# Design1.net
KiCad netlist of a schematic drawn in EAGLE
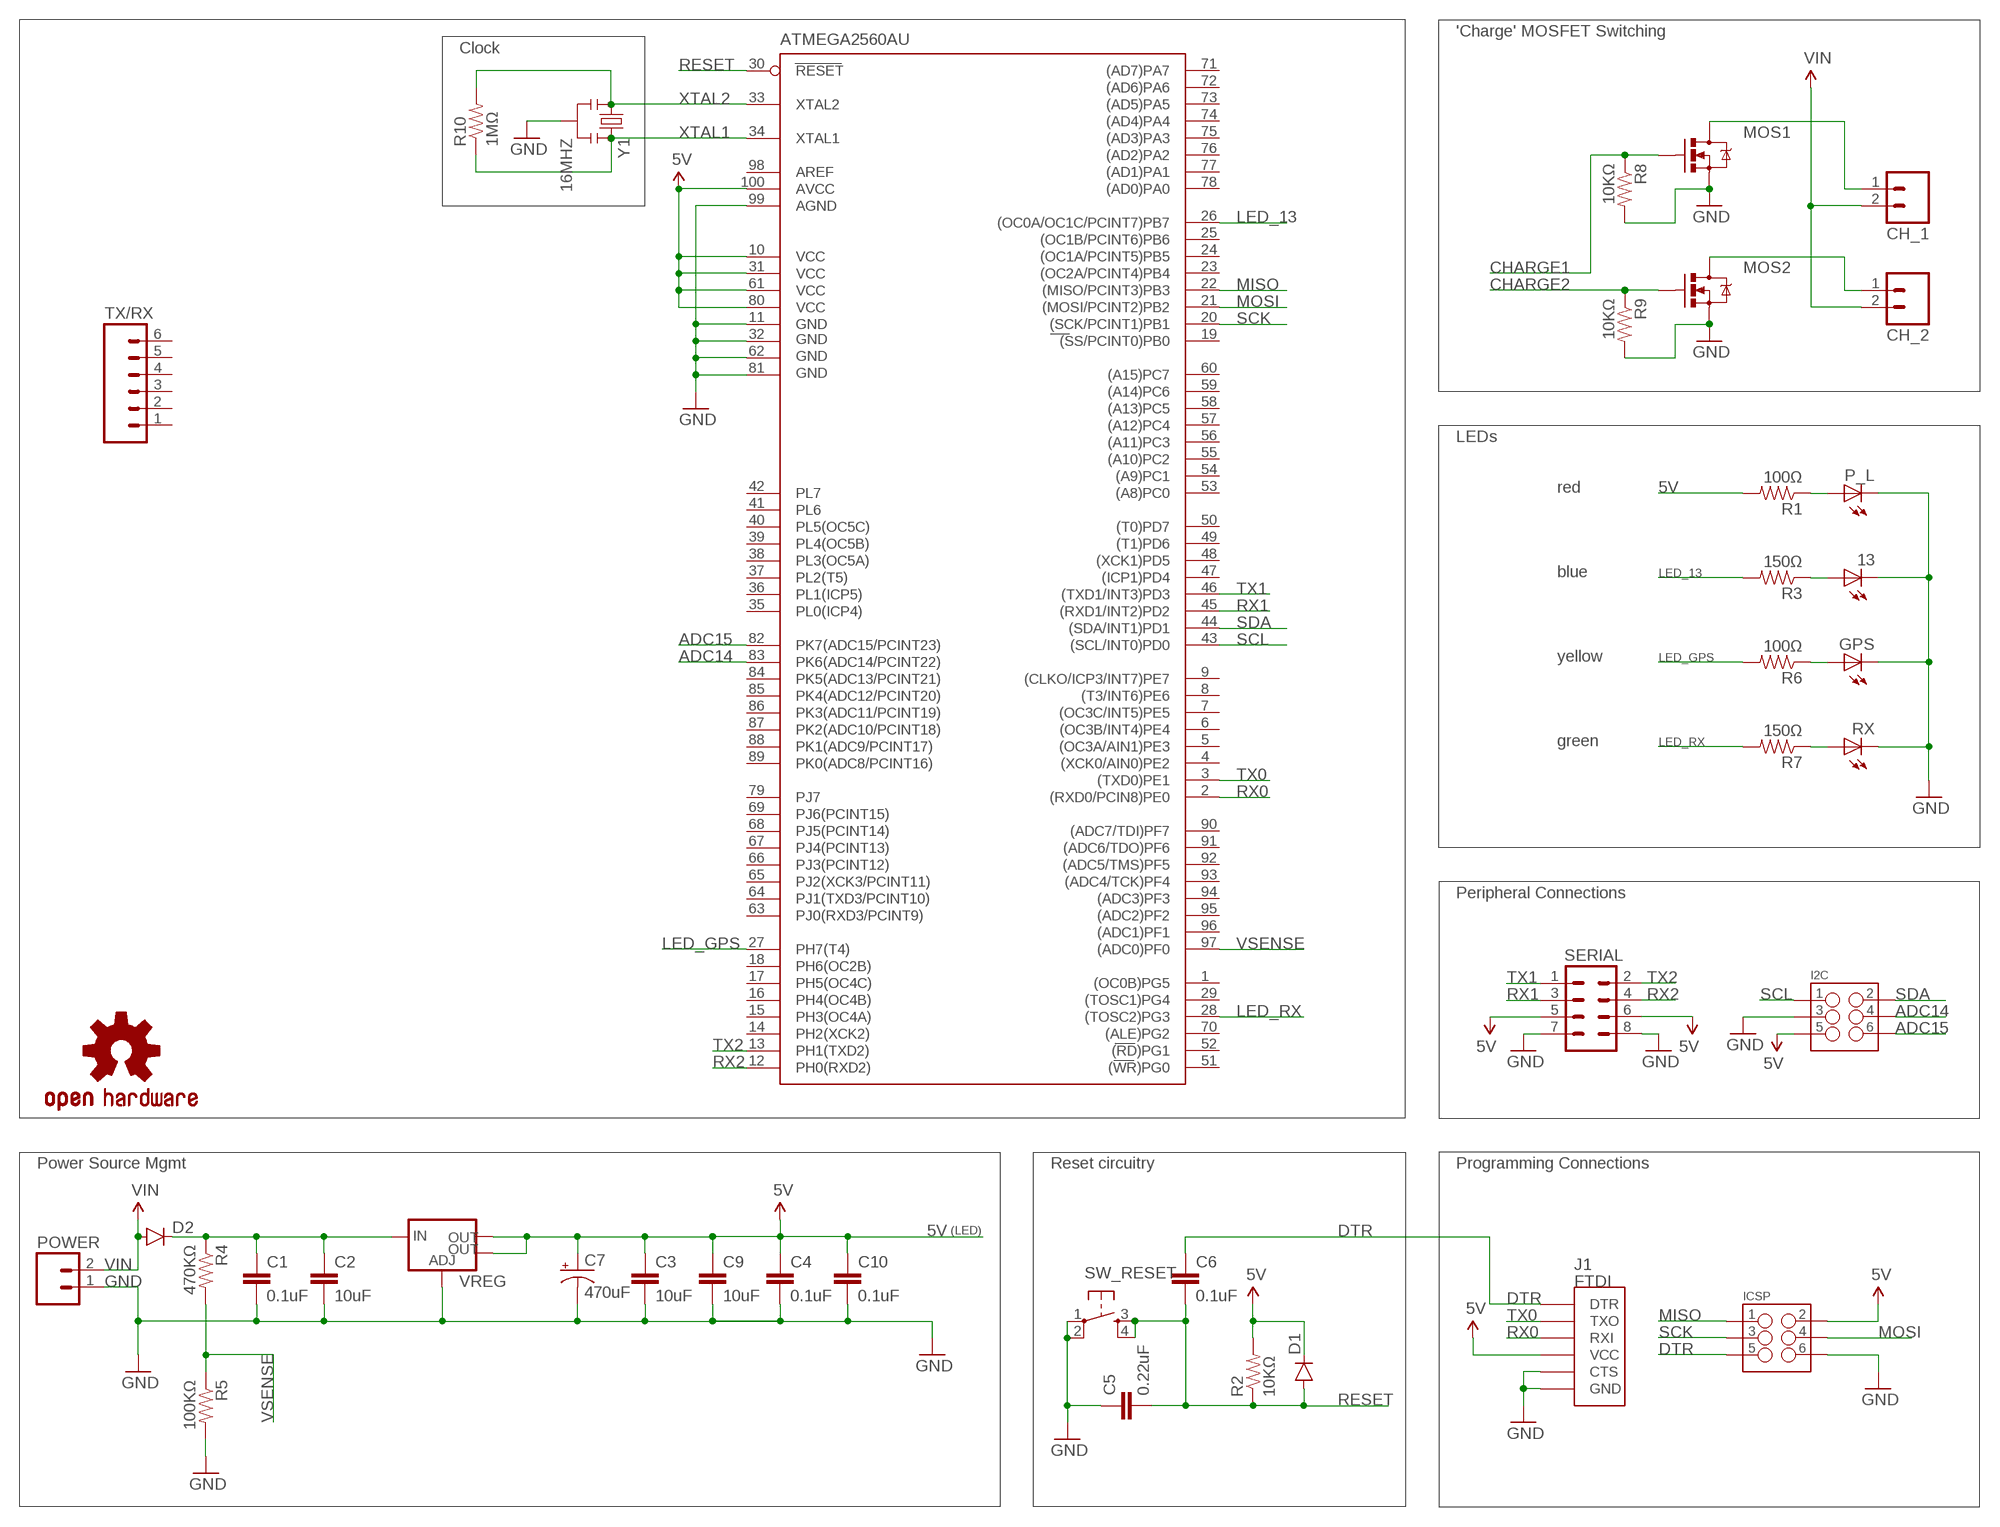
[diagram p0: schematic, sheet 1]

(export (version "E")
  (design (tool "Eeschema 10.0.6"))
  (components
    (comp (ref "13")
      (value "LEDSML0805")
      (footprint "eagle-import:SML0805")
      (libsource (lib "eagle-import") (part "LEDSML0805"))
    )
    (comp (ref "ATMEGA2560AU")
      (value "ATMEGA2560AU")
      (footprint "eagle-import:TQFP100")
      (libsource (lib "eagle-import") (part "ATMEGA2560AU"))
    )
    (comp (ref "C1")
      (value "0.1uF")
      (footprint "eagle-import:1206")
      (libsource (lib "eagle-import") (part "CAP1206"))
    )
    (comp (ref "C2")
      (value "10uF")
      (footprint "eagle-import:1206")
      (libsource (lib "eagle-import") (part "CAP1206"))
    )
    (comp (ref "C3")
      (value "10uF")
      (footprint "eagle-import:1206")
      (libsource (lib "eagle-import") (part "CAP1206"))
    )
    (comp (ref "C4")
      (value "0.1uF")
      (footprint "eagle-import:1206")
      (libsource (lib "eagle-import") (part "CAP1206"))
    )
    (comp (ref "C5")
      (value "0.22uF")
      (footprint "eagle-import:1206")
      (libsource (lib "eagle-import") (part "CAP1206"))
    )
    (comp (ref "C6")
      (value "0.1uF")
      (footprint "eagle-import:1206")
      (libsource (lib "eagle-import") (part "CAP1206"))
    )
    (comp (ref "C7")
      (value "470uF")
      (footprint "eagle-import:CPOL-RADIAL-100UF-25V")
      (libsource (lib "eagle-import") (part "CAP_POLPTH1"))
    )
    (comp (ref "C9")
      (value "10uF")
      (footprint "eagle-import:1206")
      (libsource (lib "eagle-import") (part "CAP1206"))
    )
    (comp (ref "C10")
      (value "0.1uF")
      (footprint "eagle-import:1206")
      (libsource (lib "eagle-import") (part "CAP1206"))
    )
    (comp (ref "CH_1")
      (value "M02LOCK_LONGPADS")
      (footprint "eagle-import:1X02_LOCK_LONGPADS")
      (libsource (lib "eagle-import") (part "M02LOCK_LONGPADS"))
    )
    (comp (ref "CH_2")
      (value "M02LOCK_LONGPADS")
      (footprint "eagle-import:1X02_LOCK_LONGPADS")
      (libsource (lib "eagle-import") (part "M02LOCK_LONGPADS"))
    )
    (comp (ref "D1")
      (value "DIODESMA-ALT")
      (footprint "eagle-import:SMA-DIODE_ALT")
      (libsource (lib "eagle-import") (part "DIODESMA-ALT"))
    )
    (comp (ref "D2")
      (value "DIODESMA-ALT")
      (footprint "eagle-import:SMA-DIODE_ALT")
      (libsource (lib "eagle-import") (part "DIODESMA-ALT"))
    )
    (comp (ref "GPS")
      (value "LEDSML0805")
      (footprint "eagle-import:SML0805")
      (libsource (lib "eagle-import") (part "LEDSML0805"))
    )
    (comp (ref "I2C")
      (value "M03X2FEMALE_SMD")
      (footprint "eagle-import:2X3_SMD")
      (libsource (lib "eagle-import") (part "M03X2FEMALE_SMD"))
    )
    (comp (ref "ICSP")
      (value "M03X2FEMALE_SMD")
      (footprint "eagle-import:2X3_SMD")
      (libsource (lib "eagle-import") (part "M03X2FEMALE_SMD"))
    )
    (comp (ref "J1")
      (value "FTDI")
      (footprint "eagle-import:FTDI_DEVICE_SIDE")
      (libsource (lib "eagle-import") (part "FTDI_DEVICE"))
    )
    (comp (ref "LOGO1")
      (value "OSHW-LOGOM")
      (footprint "eagle-import:OSHW-LOGO-M")
      (libsource (lib "eagle-import") (part "OSHW-LOGOM"))
    )
    (comp (ref "MOS1")
      (value "MOSFET-NCHANNELFQP30N06L")
      (footprint "eagle-import:TO220V")
      (libsource (lib "eagle-import") (part "MOSFET-NCHANNELFQP30N06L"))
    )
    (comp (ref "MOS2")
      (value "MOSFET-NCHANNELFQP30N06L")
      (footprint "eagle-import:TO220V")
      (libsource (lib "eagle-import") (part "MOSFET-NCHANNELFQP30N06L"))
    )
    (comp (ref "POWER")
      (value "M02LOCK_LONGPADS")
      (footprint "eagle-import:1X02_LOCK_LONGPADS")
      (libsource (lib "eagle-import") (part "M02LOCK_LONGPADS"))
    )
    (comp (ref "P_L")
      (value "LEDSML0805")
      (footprint "eagle-import:SML0805")
      (libsource (lib "eagle-import") (part "LEDSML0805"))
    )
    (comp (ref "R1")
      (value "100Ω")
      (footprint "eagle-import:1206")
      (libsource (lib "eagle-import") (part "RESISTOR1206"))
    )
    (comp (ref "R2")
      (value "10KΩ")
      (footprint "eagle-import:1206")
      (libsource (lib "eagle-import") (part "RESISTOR1206"))
    )
    (comp (ref "R3")
      (value "150Ω")
      (footprint "eagle-import:1206")
      (libsource (lib "eagle-import") (part "RESISTOR1206"))
    )
    (comp (ref "R4")
      (value "470KΩ")
      (footprint "eagle-import:1206")
      (libsource (lib "eagle-import") (part "RESISTOR1206"))
    )
    (comp (ref "R5")
      (value "100KΩ")
      (footprint "eagle-import:1206")
      (libsource (lib "eagle-import") (part "RESISTOR1206"))
    )
    (comp (ref "R6")
      (value "100Ω")
      (footprint "eagle-import:1206")
      (libsource (lib "eagle-import") (part "RESISTOR1206"))
    )
    (comp (ref "R7")
      (value "150Ω")
      (footprint "eagle-import:1206")
      (libsource (lib "eagle-import") (part "RESISTOR1206"))
    )
    (comp (ref "R8")
      (value "10KΩ")
      (footprint "eagle-import:1206")
      (libsource (lib "eagle-import") (part "RESISTOR1206"))
    )
    (comp (ref "R9")
      (value "10KΩ")
      (footprint "eagle-import:1206")
      (libsource (lib "eagle-import") (part "RESISTOR1206"))
    )
    (comp (ref "R10")
      (value "1MΩ")
      (footprint "eagle-import:1206")
      (libsource (lib "eagle-import") (part "RESISTOR1206"))
    )
    (comp (ref "RX")
      (value "LEDSML0805")
      (footprint "eagle-import:SML0805")
      (libsource (lib "eagle-import") (part "LEDSML0805"))
    )
    (comp (ref "SERIAL")
      (value "M04X2")
      (footprint "eagle-import:2X4")
      (libsource (lib "eagle-import") (part "M04X2"))
    )
    (comp (ref "SW_RESET")
      (value "SWITCH_SPST_4_PINSQUARE")
      (footprint "eagle-import:TACTILE-SWITCH-SMD")
      (libsource (lib "eagle-import") (part "SWITCH_SPST_4_PINSQUARE"))
    )
    (comp (ref "TX/RX")
      (value "M06SILK_FEMALE_PTH")
      (footprint "eagle-import:1X06")
      (libsource (lib "eagle-import") (part "M06SILK_FEMALE_PTH"))
    )
    (comp (ref "VREG")
      (value "V_REG_LM1117SOT223")
      (footprint "eagle-import:SOT223")
      (libsource (lib "eagle-import") (part "V_REG_LM1117SOT223"))
    )
    (comp (ref "Y1")
      (value "16MHZ")
      (footprint "eagle-import:RESONATOR-SMD")
      (libsource (lib "eagle-import") (part "RESONATOR16MHZ"))
    )
  )
  (nets
    (net (code "1") (name "/ADC14") (class "Default")
      (node (ref "ATMEGA2560AU") (pin "83") (pinfunction "PK6(ADC14/PCINT22)_83") (pintype "bidirectional"))
      (node (ref "I2C") (pin "4") (pinfunction "4_4") (pintype "bidirectional"))
    )
    (net (code "2") (name "/ADC15") (class "Default")
      (node (ref "ATMEGA2560AU") (pin "82") (pinfunction "PK7(ADC15/PCINT23)_82") (pintype "bidirectional"))
      (node (ref "I2C") (pin "6") (pinfunction "6_6") (pintype "bidirectional"))
    )
    (net (code "3") (name "/CHARGE1") (class "Default")
      (node (ref "MOS1") (pin "1") (pinfunction "G_1") (pintype "passive"))
      (node (ref "R8") (pin "1") (pinfunction "1_1") (pintype "passive"))
    )
    (net (code "4") (name "/CHARGE2") (class "Default")
      (node (ref "MOS2") (pin "1") (pinfunction "G_1") (pintype "passive"))
      (node (ref "R9") (pin "1") (pinfunction "1_1") (pintype "passive"))
    )
    (net (code "5") (name "/DTR") (class "Default")
      (node (ref "C6") (pin "1") (pinfunction "1_1") (pintype "passive"))
      (node (ref "ICSP") (pin "5") (pinfunction "5_5") (pintype "bidirectional"))
      (node (ref "J1") (pin "P$1") (pinfunction "DTR_P$1") (pintype "bidirectional"))
    )
    (net (code "6") (name "/LED_13") (class "Default")
      (node (ref "ATMEGA2560AU") (pin "26") (pinfunction "(OC0A/OC1C/PCINT7)PB7_26") (pintype "bidirectional"))
      (node (ref "R3") (pin "2") (pinfunction "2_2") (pintype "passive"))
    )
    (net (code "7") (name "/LED_GPS") (class "Default")
      (node (ref "ATMEGA2560AU") (pin "27") (pinfunction "PH7(T4)_27") (pintype "bidirectional"))
      (node (ref "R6") (pin "2") (pinfunction "2_2") (pintype "passive"))
    )
    (net (code "8") (name "/LED_RX") (class "Default")
      (node (ref "ATMEGA2560AU") (pin "28") (pinfunction "(TOSC2)PG3_28") (pintype "bidirectional"))
      (node (ref "R7") (pin "2") (pinfunction "2_2") (pintype "passive"))
    )
    (net (code "9") (name "/MISO") (class "Default")
      (node (ref "ATMEGA2560AU") (pin "22") (pinfunction "(MISO/PCINT3)PB3_22") (pintype "bidirectional"))
      (node (ref "ICSP") (pin "1") (pinfunction "1_1") (pintype "bidirectional"))
    )
    (net (code "10") (name "/MOSI") (class "Default")
      (node (ref "ATMEGA2560AU") (pin "21") (pinfunction "(MOSI/PCINT2)PB2_21") (pintype "bidirectional"))
      (node (ref "ICSP") (pin "4") (pinfunction "4_4") (pintype "bidirectional"))
    )
    (net (code "11") (name "/RESET") (class "Default")
      (node (ref "ATMEGA2560AU") (pin "30") (pinfunction "RESET_30") (pintype "input"))
      (node (ref "C5") (pin "2") (pinfunction "2_2") (pintype "passive"))
      (node (ref "C6") (pin "2") (pinfunction "2_2") (pintype "passive"))
      (node (ref "D1") (pin "A") (pinfunction "A_A") (pintype "passive"))
      (node (ref "R2") (pin "1") (pinfunction "1_1") (pintype "passive"))
      (node (ref "SW_RESET") (pin "3") (pinfunction "3_3") (pintype "passive"))
      (node (ref "SW_RESET") (pin "4") (pinfunction "4_4") (pintype "passive"))
    )
    (net (code "12") (name "/RX0") (class "Default")
      (node (ref "ATMEGA2560AU") (pin "2") (pinfunction "(RXD0/PCIN8)PE0_2") (pintype "bidirectional"))
      (node (ref "J1") (pin "P$3") (pinfunction "RXI_P$3") (pintype "bidirectional"))
    )
    (net (code "13") (name "/RX1") (class "Default")
      (node (ref "ATMEGA2560AU") (pin "45") (pinfunction "(RXD1/INT2)PD2_45") (pintype "bidirectional"))
      (node (ref "SERIAL") (pin "3") (pinfunction "3_3") (pintype "passive"))
    )
    (net (code "14") (name "/RX2") (class "Default")
      (node (ref "ATMEGA2560AU") (pin "12") (pinfunction "PH0(RXD2)_12") (pintype "bidirectional"))
      (node (ref "SERIAL") (pin "4") (pinfunction "4_4") (pintype "passive"))
    )
    (net (code "15") (name "/SCK") (class "Default")
      (node (ref "ATMEGA2560AU") (pin "20") (pinfunction "(SCK/PCINT1)PB1_20") (pintype "bidirectional"))
      (node (ref "ICSP") (pin "3") (pinfunction "3_3") (pintype "bidirectional"))
    )
    (net (code "16") (name "/SCL") (class "Default")
      (node (ref "ATMEGA2560AU") (pin "43") (pinfunction "(SCL/INT0)PD0_43") (pintype "bidirectional"))
      (node (ref "I2C") (pin "1") (pinfunction "1_1") (pintype "bidirectional"))
    )
    (net (code "17") (name "/SDA") (class "Default")
      (node (ref "ATMEGA2560AU") (pin "44") (pinfunction "(SDA/INT1)PD1_44") (pintype "bidirectional"))
      (node (ref "I2C") (pin "2") (pinfunction "2_2") (pintype "bidirectional"))
    )
    (net (code "18") (name "/TX0") (class "Default")
      (node (ref "ATMEGA2560AU") (pin "3") (pinfunction "(TXD0)PE1_3") (pintype "bidirectional"))
      (node (ref "J1") (pin "P$2") (pinfunction "TXO_P$2") (pintype "bidirectional"))
    )
    (net (code "19") (name "/TX1") (class "Default")
      (node (ref "ATMEGA2560AU") (pin "46") (pinfunction "(TXD1/INT3)PD3_46") (pintype "bidirectional"))
      (node (ref "SERIAL") (pin "1") (pinfunction "1_1") (pintype "passive"))
    )
    (net (code "20") (name "/TX2") (class "Default")
      (node (ref "ATMEGA2560AU") (pin "13") (pinfunction "PH1(TXD2)_13") (pintype "bidirectional"))
      (node (ref "SERIAL") (pin "2") (pinfunction "2_2") (pintype "passive"))
    )
    (net (code "21") (name "/VSENSE") (class "Default")
      (node (ref "ATMEGA2560AU") (pin "97") (pinfunction "(ADC0)PF0_97") (pintype "bidirectional"))
      (node (ref "R4") (pin "2") (pinfunction "2_2") (pintype "passive"))
      (node (ref "R5") (pin "1") (pinfunction "1_1") (pintype "passive"))
    )
    (net (code "22") (name "/XTAL1") (class "Default")
      (node (ref "ATMEGA2560AU") (pin "34") (pinfunction "XTAL1_34") (pintype "input"))
      (node (ref "R10") (pin "1") (pinfunction "1_1") (pintype "passive"))
      (node (ref "Y1") (pin "3") (pinfunction "3_3") (pintype "passive"))
    )
    (net (code "23") (name "/XTAL2") (class "Default")
      (node (ref "ATMEGA2560AU") (pin "33") (pinfunction "XTAL2_33") (pintype "output"))
      (node (ref "R10") (pin "2") (pinfunction "2_2") (pintype "passive"))
      (node (ref "Y1") (pin "1") (pinfunction "1_1") (pintype "passive"))
    )
    (net (code "24") (name "5V") (class "Default")
      (node (ref "ATMEGA2560AU") (pin "10") (pinfunction "VCC_10") (pintype "power_in"))
      (node (ref "ATMEGA2560AU") (pin "100") (pinfunction "AVCC_100") (pintype "power_in"))
      (node (ref "ATMEGA2560AU") (pin "31") (pinfunction "VCC1_31") (pintype "power_in"))
      (node (ref "ATMEGA2560AU") (pin "61") (pinfunction "VCC2_61") (pintype "power_in"))
      (node (ref "ATMEGA2560AU") (pin "80") (pinfunction "VCC3_80") (pintype "power_in"))
      (node (ref "C10") (pin "1") (pinfunction "1_1") (pintype "passive"))
      (node (ref "C3") (pin "1") (pinfunction "1_1") (pintype "passive"))
      (node (ref "C4") (pin "1") (pinfunction "1_1") (pintype "passive"))
      (node (ref "C7") (pin "1") (pinfunction "+_1") (pintype "passive"))
      (node (ref "C9") (pin "1") (pinfunction "1_1") (pintype "passive"))
      (node (ref "D1") (pin "C") (pinfunction "C_C") (pintype "passive"))
      (node (ref "I2C") (pin "5") (pinfunction "5_5") (pintype "bidirectional"))
      (node (ref "ICSP") (pin "2") (pinfunction "2_2") (pintype "bidirectional"))
      (node (ref "J1") (pin "P$4") (pinfunction "VCC_P$4") (pintype "bidirectional"))
      (node (ref "R1") (pin "2") (pinfunction "2_2") (pintype "passive"))
      (node (ref "R2") (pin "2") (pinfunction "2_2") (pintype "passive"))
      (node (ref "SERIAL") (pin "5") (pinfunction "5_5") (pintype "passive"))
      (node (ref "SERIAL") (pin "6") (pinfunction "6_6") (pintype "passive"))
      (node (ref "VREG") (pin "2") (pinfunction "OUT_2") (pintype "output"))
      (node (ref "VREG") (pin "4") (pinfunction "OUT_4") (pintype "output"))
    )
    (net (code "25") (name "GND") (class "Default")
      (node (ref "13") (pin "C") (pinfunction "C_C") (pintype "passive"))
      (node (ref "ATMEGA2560AU") (pin "11") (pinfunction "GND_11") (pintype "power_in"))
      (node (ref "ATMEGA2560AU") (pin "32") (pinfunction "GND1_32") (pintype "power_in"))
      (node (ref "ATMEGA2560AU") (pin "62") (pinfunction "GND2_62") (pintype "power_in"))
      (node (ref "ATMEGA2560AU") (pin "81") (pinfunction "GND3_81") (pintype "power_in"))
      (node (ref "ATMEGA2560AU") (pin "99") (pinfunction "AGND_99") (pintype "power_in"))
      (node (ref "C1") (pin "2") (pinfunction "2_2") (pintype "passive"))
      (node (ref "C10") (pin "2") (pinfunction "2_2") (pintype "passive"))
      (node (ref "C2") (pin "2") (pinfunction "2_2") (pintype "passive"))
      (node (ref "C3") (pin "2") (pinfunction "2_2") (pintype "passive"))
      (node (ref "C4") (pin "2") (pinfunction "2_2") (pintype "passive"))
      (node (ref "C5") (pin "1") (pinfunction "1_1") (pintype "passive"))
      (node (ref "C7") (pin "2") (pinfunction "-_2") (pintype "passive"))
      (node (ref "C9") (pin "2") (pinfunction "2_2") (pintype "passive"))
      (node (ref "GPS") (pin "C") (pinfunction "C_C") (pintype "passive"))
      (node (ref "I2C") (pin "3") (pinfunction "3_3") (pintype "bidirectional"))
      (node (ref "ICSP") (pin "6") (pinfunction "6_6") (pintype "bidirectional"))
      (node (ref "J1") (pin "P$5") (pinfunction "CTS_P$5") (pintype "bidirectional"))
      (node (ref "J1") (pin "P$6") (pinfunction "GND_P$6") (pintype "bidirectional"))
      (node (ref "MOS1") (pin "3") (pinfunction "S_3") (pintype "passive"))
      (node (ref "MOS2") (pin "3") (pinfunction "S_3") (pintype "passive"))
      (node (ref "POWER") (pin "1") (pinfunction "1_1") (pintype "passive"))
      (node (ref "P_L") (pin "C") (pinfunction "C_C") (pintype "passive"))
      (node (ref "R5") (pin "2") (pinfunction "2_2") (pintype "passive"))
      (node (ref "R8") (pin "2") (pinfunction "2_2") (pintype "passive"))
      (node (ref "R9") (pin "2") (pinfunction "2_2") (pintype "passive"))
      (node (ref "RX") (pin "C") (pinfunction "C_C") (pintype "passive"))
      (node (ref "SERIAL") (pin "7") (pinfunction "7_7") (pintype "passive"))
      (node (ref "SERIAL") (pin "8") (pinfunction "8_8") (pintype "passive"))
      (node (ref "SW_RESET") (pin "1") (pinfunction "1_1") (pintype "passive"))
      (node (ref "SW_RESET") (pin "2") (pinfunction "2_2") (pintype "passive"))
      (node (ref "VREG") (pin "1") (pinfunction "ADJ_1") (pintype "input"))
      (node (ref "Y1") (pin "2") (pinfunction "2_2") (pintype "passive"))
    )
    (net (code "26") (name "Net-(13-PadA)") (class "Default")
      (node (ref "13") (pin "A") (pinfunction "A_A") (pintype "passive"))
      (node (ref "R3") (pin "1") (pinfunction "1_1") (pintype "passive"))
    )
    (net (code "27") (name "Net-(GPS-PadA)") (class "Default")
      (node (ref "GPS") (pin "A") (pinfunction "A_A") (pintype "passive"))
      (node (ref "R6") (pin "1") (pinfunction "1_1") (pintype "passive"))
    )
    (net (code "28") (name "Net-(MOS1-D)") (class "Default")
      (node (ref "CH_1") (pin "1") (pinfunction "1_1") (pintype "passive"))
      (node (ref "MOS1") (pin "2") (pinfunction "D_2") (pintype "passive"))
    )
    (net (code "29") (name "Net-(MOS2-D)") (class "Default")
      (node (ref "CH_2") (pin "1") (pinfunction "1_1") (pintype "passive"))
      (node (ref "MOS2") (pin "2") (pinfunction "D_2") (pintype "passive"))
    )
    (net (code "30") (name "Net-(P_L-PadA)") (class "Default")
      (node (ref "P_L") (pin "A") (pinfunction "A_A") (pintype "passive"))
      (node (ref "R1") (pin "1") (pinfunction "1_1") (pintype "passive"))
    )
    (net (code "31") (name "Net-(R7-Pad1)") (class "Default")
      (node (ref "R7") (pin "1") (pinfunction "1_1") (pintype "passive"))
      (node (ref "RX") (pin "A") (pinfunction "A_A") (pintype "passive"))
    )
    (net (code "32") (name "Net-(VREG-IN)") (class "Default")
      (node (ref "C1") (pin "1") (pinfunction "1_1") (pintype "passive"))
      (node (ref "C2") (pin "1") (pinfunction "1_1") (pintype "passive"))
      (node (ref "D2") (pin "C") (pinfunction "C_C") (pintype "passive"))
      (node (ref "R4") (pin "1") (pinfunction "1_1") (pintype "passive"))
      (node (ref "VREG") (pin "3") (pinfunction "IN_3") (pintype "input"))
    )
    (net (code "33") (name "VIN") (class "Default")
      (node (ref "CH_1") (pin "2") (pinfunction "2_2") (pintype "passive"))
      (node (ref "CH_2") (pin "2") (pinfunction "2_2") (pintype "passive"))
      (node (ref "D2") (pin "A") (pinfunction "A_A") (pintype "passive"))
      (node (ref "POWER") (pin "2") (pinfunction "2_2") (pintype "passive"))
    )
    (net (code "34") (name "unconnected-(ATMEGA2560AU-(A8)PC0-Pad53)") (class "Default")
      (node (ref "ATMEGA2560AU") (pin "53") (pinfunction "(A8)PC0_53") (pintype "bidirectional"))
    )
    (net (code "35") (name "unconnected-(ATMEGA2560AU-(A9)PC1-Pad54)") (class "Default")
      (node (ref "ATMEGA2560AU") (pin "54") (pinfunction "(A9)PC1_54") (pintype "bidirectional"))
    )
    (net (code "36") (name "unconnected-(ATMEGA2560AU-(A10)PC2-Pad55)") (class "Default")
      (node (ref "ATMEGA2560AU") (pin "55") (pinfunction "(A10)PC2_55") (pintype "bidirectional"))
    )
    (net (code "37") (name "unconnected-(ATMEGA2560AU-(A11)PC3-Pad56)") (class "Default")
      (node (ref "ATMEGA2560AU") (pin "56") (pinfunction "(A11)PC3_56") (pintype "bidirectional"))
    )
    (net (code "38") (name "unconnected-(ATMEGA2560AU-(A12)PC4-Pad57)") (class "Default")
      (node (ref "ATMEGA2560AU") (pin "57") (pinfunction "(A12)PC4_57") (pintype "bidirectional"))
    )
    (net (code "39") (name "unconnected-(ATMEGA2560AU-(A13)PC5-Pad58)") (class "Default")
      (node (ref "ATMEGA2560AU") (pin "58") (pinfunction "(A13)PC5_58") (pintype "bidirectional"))
    )
    (net (code "40") (name "unconnected-(ATMEGA2560AU-(A14)PC6-Pad59)") (class "Default")
      (node (ref "ATMEGA2560AU") (pin "59") (pinfunction "(A14)PC6_59") (pintype "bidirectional"))
    )
    (net (code "41") (name "unconnected-(ATMEGA2560AU-(A15)PC7-Pad60)") (class "Default")
      (node (ref "ATMEGA2560AU") (pin "60") (pinfunction "(A15)PC7_60") (pintype "bidirectional"))
    )
    (net (code "42") (name "unconnected-(ATMEGA2560AU-(AD0)PA0-Pad78)") (class "Default")
      (node (ref "ATMEGA2560AU") (pin "78") (pinfunction "(AD0)PA0_78") (pintype "bidirectional"))
    )
    (net (code "43") (name "unconnected-(ATMEGA2560AU-(AD1)PA1-Pad77)") (class "Default")
      (node (ref "ATMEGA2560AU") (pin "77") (pinfunction "(AD1)PA1_77") (pintype "bidirectional"))
    )
    (net (code "44") (name "unconnected-(ATMEGA2560AU-(AD2)PA2-Pad76)") (class "Default")
      (node (ref "ATMEGA2560AU") (pin "76") (pinfunction "(AD2)PA2_76") (pintype "bidirectional"))
    )
    (net (code "45") (name "unconnected-(ATMEGA2560AU-(AD3)PA3-Pad75)") (class "Default")
      (node (ref "ATMEGA2560AU") (pin "75") (pinfunction "(AD3)PA3_75") (pintype "bidirectional"))
    )
    (net (code "46") (name "unconnected-(ATMEGA2560AU-(AD4)PA4-Pad74)") (class "Default")
      (node (ref "ATMEGA2560AU") (pin "74") (pinfunction "(AD4)PA4_74") (pintype "bidirectional"))
    )
    (net (code "47") (name "unconnected-(ATMEGA2560AU-(AD5)PA5-Pad73)") (class "Default")
      (node (ref "ATMEGA2560AU") (pin "73") (pinfunction "(AD5)PA5_73") (pintype "bidirectional"))
    )
    (net (code "48") (name "unconnected-(ATMEGA2560AU-(AD6)PA6-Pad72)") (class "Default")
      (node (ref "ATMEGA2560AU") (pin "72") (pinfunction "(AD6)PA6_72") (pintype "bidirectional"))
    )
    (net (code "49") (name "unconnected-(ATMEGA2560AU-(AD7)PA7-Pad71)") (class "Default")
      (node (ref "ATMEGA2560AU") (pin "71") (pinfunction "(AD7)PA7_71") (pintype "bidirectional"))
    )
    (net (code "50") (name "unconnected-(ATMEGA2560AU-(ADC1)PF1-Pad96)") (class "Default")
      (node (ref "ATMEGA2560AU") (pin "96") (pinfunction "(ADC1)PF1_96") (pintype "bidirectional"))
    )
    (net (code "51") (name "unconnected-(ATMEGA2560AU-(ADC2)PF2-Pad95)") (class "Default")
      (node (ref "ATMEGA2560AU") (pin "95") (pinfunction "(ADC2)PF2_95") (pintype "bidirectional"))
    )
    (net (code "52") (name "unconnected-(ATMEGA2560AU-(ADC3)PF3-Pad94)") (class "Default")
      (node (ref "ATMEGA2560AU") (pin "94") (pinfunction "(ADC3)PF3_94") (pintype "bidirectional"))
    )
    (net (code "53") (name "unconnected-(ATMEGA2560AU-(ADC4{slash}TCK)PF4-Pad93)") (class "Default")
      (node (ref "ATMEGA2560AU") (pin "93") (pinfunction "(ADC4/TCK)PF4_93") (pintype "bidirectional"))
    )
    (net (code "54") (name "unconnected-(ATMEGA2560AU-(ADC5{slash}TMS)PF5-Pad92)") (class "Default")
      (node (ref "ATMEGA2560AU") (pin "92") (pinfunction "(ADC5/TMS)PF5_92") (pintype "bidirectional"))
    )
    (net (code "55") (name "unconnected-(ATMEGA2560AU-(ADC6{slash}TDO)PF6-Pad91)") (class "Default")
      (node (ref "ATMEGA2560AU") (pin "91") (pinfunction "(ADC6/TDO)PF6_91") (pintype "bidirectional"))
    )
    (net (code "56") (name "unconnected-(ATMEGA2560AU-(ADC7{slash}TDI)PF7-Pad90)") (class "Default")
      (node (ref "ATMEGA2560AU") (pin "90") (pinfunction "(ADC7/TDI)PF7_90") (pintype "bidirectional"))
    )
    (net (code "57") (name "unconnected-(ATMEGA2560AU-(ALE)PG2-Pad70)") (class "Default")
      (node (ref "ATMEGA2560AU") (pin "70") (pinfunction "(ALE)PG2_70") (pintype "bidirectional"))
    )
    (net (code "58") (name "unconnected-(ATMEGA2560AU-(CLKO{slash}ICP3{slash}INT7)PE7-Pad9)") (class "Default")
      (node (ref "ATMEGA2560AU") (pin "9") (pinfunction "(CLKO/ICP3/INT7)PE7_9") (pintype "bidirectional"))
    )
    (net (code "59") (name "unconnected-(ATMEGA2560AU-(ICP1)PD4-Pad47)") (class "Default")
      (node (ref "ATMEGA2560AU") (pin "47") (pinfunction "(ICP1)PD4_47") (pintype "bidirectional"))
    )
    (net (code "60") (name "unconnected-(ATMEGA2560AU-(OC0B)PG5-Pad1)") (class "Default")
      (node (ref "ATMEGA2560AU") (pin "1") (pinfunction "(OC0B)PG5_1") (pintype "bidirectional"))
    )
    (net (code "61") (name "unconnected-(ATMEGA2560AU-(OC1A{slash}PCINT5)PB5-Pad24)") (class "Default")
      (node (ref "ATMEGA2560AU") (pin "24") (pinfunction "(OC1A/PCINT5)PB5_24") (pintype "bidirectional"))
    )
    (net (code "62") (name "unconnected-(ATMEGA2560AU-(OC1B{slash}PCINT6)PB6-Pad25)") (class "Default")
      (node (ref "ATMEGA2560AU") (pin "25") (pinfunction "(OC1B/PCINT6)PB6_25") (pintype "bidirectional"))
    )
    (net (code "63") (name "unconnected-(ATMEGA2560AU-(OC2A{slash}PCINT4)PB4-Pad23)") (class "Default")
      (node (ref "ATMEGA2560AU") (pin "23") (pinfunction "(OC2A/PCINT4)PB4_23") (pintype "bidirectional"))
    )
    (net (code "64") (name "unconnected-(ATMEGA2560AU-(OC3A{slash}AIN1)PE3-Pad5)") (class "Default")
      (node (ref "ATMEGA2560AU") (pin "5") (pinfunction "(OC3A/AIN1)PE3_5") (pintype "bidirectional"))
    )
    (net (code "65") (name "unconnected-(ATMEGA2560AU-(OC3B{slash}INT4)PE4-Pad6)") (class "Default")
      (node (ref "ATMEGA2560AU") (pin "6") (pinfunction "(OC3B/INT4)PE4_6") (pintype "bidirectional"))
    )
    (net (code "66") (name "unconnected-(ATMEGA2560AU-(OC3C{slash}INT5)PE5-Pad7)") (class "Default")
      (node (ref "ATMEGA2560AU") (pin "7") (pinfunction "(OC3C/INT5)PE5_7") (pintype "bidirectional"))
    )
    (net (code "67") (name "unconnected-(ATMEGA2560AU-(RD)PG1-Pad52)") (class "Default")
      (node (ref "ATMEGA2560AU") (pin "52") (pinfunction "(RD)PG1_52") (pintype "bidirectional"))
    )
    (net (code "68") (name "unconnected-(ATMEGA2560AU-(SS{slash}PCINT0)PB0-Pad19)") (class "Default")
      (node (ref "ATMEGA2560AU") (pin "19") (pinfunction "(SS/PCINT0)PB0_19") (pintype "bidirectional"))
    )
    (net (code "69") (name "unconnected-(ATMEGA2560AU-(T0)PD7-Pad50)") (class "Default")
      (node (ref "ATMEGA2560AU") (pin "50") (pinfunction "(T0)PD7_50") (pintype "bidirectional"))
    )
    (net (code "70") (name "unconnected-(ATMEGA2560AU-(T1)PD6-Pad49)") (class "Default")
      (node (ref "ATMEGA2560AU") (pin "49") (pinfunction "(T1)PD6_49") (pintype "bidirectional"))
    )
    (net (code "71") (name "unconnected-(ATMEGA2560AU-(T3{slash}INT6)PE6-Pad8)") (class "Default")
      (node (ref "ATMEGA2560AU") (pin "8") (pinfunction "(T3/INT6)PE6_8") (pintype "bidirectional"))
    )
    (net (code "72") (name "unconnected-(ATMEGA2560AU-(TOSC1)PG4-Pad29)") (class "Default")
      (node (ref "ATMEGA2560AU") (pin "29") (pinfunction "(TOSC1)PG4_29") (pintype "bidirectional"))
    )
    (net (code "73") (name "unconnected-(ATMEGA2560AU-(WR)PG0-Pad51)") (class "Default")
      (node (ref "ATMEGA2560AU") (pin "51") (pinfunction "(WR)PG0_51") (pintype "bidirectional"))
    )
    (net (code "74") (name "unconnected-(ATMEGA2560AU-(XCK0{slash}AIN0)PE2-Pad4)") (class "Default")
      (node (ref "ATMEGA2560AU") (pin "4") (pinfunction "(XCK0/AIN0)PE2_4") (pintype "bidirectional"))
    )
    (net (code "75") (name "unconnected-(ATMEGA2560AU-(XCK1)PD5-Pad48)") (class "Default")
      (node (ref "ATMEGA2560AU") (pin "48") (pinfunction "(XCK1)PD5_48") (pintype "bidirectional"))
    )
    (net (code "76") (name "unconnected-(ATMEGA2560AU-AREF-Pad98)") (class "Default")
      (node (ref "ATMEGA2560AU") (pin "98") (pinfunction "AREF_98") (pintype "bidirectional"))
    )
    (net (code "77") (name "unconnected-(ATMEGA2560AU-PH2(XCK2)-Pad14)") (class "Default")
      (node (ref "ATMEGA2560AU") (pin "14") (pinfunction "PH2(XCK2)_14") (pintype "bidirectional"))
    )
    (net (code "78") (name "unconnected-(ATMEGA2560AU-PH3(OC4A)-Pad15)") (class "Default")
      (node (ref "ATMEGA2560AU") (pin "15") (pinfunction "PH3(OC4A)_15") (pintype "bidirectional"))
    )
    (net (code "79") (name "unconnected-(ATMEGA2560AU-PH4(OC4B)-Pad16)") (class "Default")
      (node (ref "ATMEGA2560AU") (pin "16") (pinfunction "PH4(OC4B)_16") (pintype "bidirectional"))
    )
    (net (code "80") (name "unconnected-(ATMEGA2560AU-PH5(OC4C)-Pad17)") (class "Default")
      (node (ref "ATMEGA2560AU") (pin "17") (pinfunction "PH5(OC4C)_17") (pintype "bidirectional"))
    )
    (net (code "81") (name "unconnected-(ATMEGA2560AU-PH6(OC2B)-Pad18)") (class "Default")
      (node (ref "ATMEGA2560AU") (pin "18") (pinfunction "PH6(OC2B)_18") (pintype "bidirectional"))
    )
    (net (code "82") (name "unconnected-(ATMEGA2560AU-PJ0(RXD3{slash}PCINT9)-Pad63)") (class "Default")
      (node (ref "ATMEGA2560AU") (pin "63") (pinfunction "PJ0(RXD3/PCINT9)_63") (pintype "bidirectional"))
    )
    (net (code "83") (name "unconnected-(ATMEGA2560AU-PJ1(TXD3{slash}PCINT10)-Pad64)") (class "Default")
      (node (ref "ATMEGA2560AU") (pin "64") (pinfunction "PJ1(TXD3/PCINT10)_64") (pintype "bidirectional"))
    )
    (net (code "84") (name "unconnected-(ATMEGA2560AU-PJ2(XCK3{slash}PCINT11)-Pad65)") (class "Default")
      (node (ref "ATMEGA2560AU") (pin "65") (pinfunction "PJ2(XCK3/PCINT11)_65") (pintype "bidirectional"))
    )
    (net (code "85") (name "unconnected-(ATMEGA2560AU-PJ3(PCINT12)-Pad66)") (class "Default")
      (node (ref "ATMEGA2560AU") (pin "66") (pinfunction "PJ3(PCINT12)_66") (pintype "bidirectional"))
    )
    (net (code "86") (name "unconnected-(ATMEGA2560AU-PJ4(PCINT13)-Pad67)") (class "Default")
      (node (ref "ATMEGA2560AU") (pin "67") (pinfunction "PJ4(PCINT13)_67") (pintype "bidirectional"))
    )
    (net (code "87") (name "unconnected-(ATMEGA2560AU-PJ5(PCINT14)-Pad68)") (class "Default")
      (node (ref "ATMEGA2560AU") (pin "68") (pinfunction "PJ5(PCINT14)_68") (pintype "bidirectional"))
    )
    (net (code "88") (name "unconnected-(ATMEGA2560AU-PJ6(PCINT15)-Pad69)") (class "Default")
      (node (ref "ATMEGA2560AU") (pin "69") (pinfunction "PJ6(PCINT15)_69") (pintype "bidirectional"))
    )
    (net (code "89") (name "unconnected-(ATMEGA2560AU-PJ7-Pad79)") (class "Default")
      (node (ref "ATMEGA2560AU") (pin "79") (pinfunction "PJ7_79") (pintype "bidirectional"))
    )
    (net (code "90") (name "unconnected-(ATMEGA2560AU-PK0(ADC8{slash}PCINT16)-Pad89)") (class "Default")
      (node (ref "ATMEGA2560AU") (pin "89") (pinfunction "PK0(ADC8/PCINT16)_89") (pintype "bidirectional"))
    )
    (net (code "91") (name "unconnected-(ATMEGA2560AU-PK1(ADC9{slash}PCINT17)-Pad88)") (class "Default")
      (node (ref "ATMEGA2560AU") (pin "88") (pinfunction "PK1(ADC9/PCINT17)_88") (pintype "bidirectional"))
    )
    (net (code "92") (name "unconnected-(ATMEGA2560AU-PK2(ADC10{slash}PCINT18)-Pad87)") (class "Default")
      (node (ref "ATMEGA2560AU") (pin "87") (pinfunction "PK2(ADC10/PCINT18)_87") (pintype "bidirectional"))
    )
    (net (code "93") (name "unconnected-(ATMEGA2560AU-PK3(ADC11{slash}PCINT19)-Pad86)") (class "Default")
      (node (ref "ATMEGA2560AU") (pin "86") (pinfunction "PK3(ADC11/PCINT19)_86") (pintype "bidirectional"))
    )
    (net (code "94") (name "unconnected-(ATMEGA2560AU-PK4(ADC12{slash}PCINT20)-Pad85)") (class "Default")
      (node (ref "ATMEGA2560AU") (pin "85") (pinfunction "PK4(ADC12/PCINT20)_85") (pintype "bidirectional"))
    )
    (net (code "95") (name "unconnected-(ATMEGA2560AU-PK5(ADC13{slash}PCINT21)-Pad84)") (class "Default")
      (node (ref "ATMEGA2560AU") (pin "84") (pinfunction "PK5(ADC13/PCINT21)_84") (pintype "bidirectional"))
    )
    (net (code "96") (name "unconnected-(ATMEGA2560AU-PL0(ICP4)-Pad35)") (class "Default")
      (node (ref "ATMEGA2560AU") (pin "35") (pinfunction "PL0(ICP4)_35") (pintype "bidirectional"))
    )
    (net (code "97") (name "unconnected-(ATMEGA2560AU-PL1(ICP5)-Pad36)") (class "Default")
      (node (ref "ATMEGA2560AU") (pin "36") (pinfunction "PL1(ICP5)_36") (pintype "bidirectional"))
    )
    (net (code "98") (name "unconnected-(ATMEGA2560AU-PL2(T5)-Pad37)") (class "Default")
      (node (ref "ATMEGA2560AU") (pin "37") (pinfunction "PL2(T5)_37") (pintype "bidirectional"))
    )
    (net (code "99") (name "unconnected-(ATMEGA2560AU-PL3(OC5A)-Pad38)") (class "Default")
      (node (ref "ATMEGA2560AU") (pin "38") (pinfunction "PL3(OC5A)_38") (pintype "bidirectional"))
    )
    (net (code "100") (name "unconnected-(ATMEGA2560AU-PL4(OC5B)-Pad39)") (class "Default")
      (node (ref "ATMEGA2560AU") (pin "39") (pinfunction "PL4(OC5B)_39") (pintype "bidirectional"))
    )
    (net (code "101") (name "unconnected-(ATMEGA2560AU-PL5(OC5C)-Pad40)") (class "Default")
      (node (ref "ATMEGA2560AU") (pin "40") (pinfunction "PL5(OC5C)_40") (pintype "bidirectional"))
    )
    (net (code "102") (name "unconnected-(ATMEGA2560AU-PL6-Pad41)") (class "Default")
      (node (ref "ATMEGA2560AU") (pin "41") (pinfunction "PL6_41") (pintype "bidirectional"))
    )
    (net (code "103") (name "unconnected-(ATMEGA2560AU-PL7-Pad42)") (class "Default")
      (node (ref "ATMEGA2560AU") (pin "42") (pinfunction "PL7_42") (pintype "bidirectional"))
    )
    (net (code "104") (name "unconnected-(TX/RX-Pad1)") (class "Default")
      (node (ref "TX/RX") (pin "1") (pinfunction "1_1") (pintype "passive"))
    )
    (net (code "105") (name "unconnected-(TX/RX-Pad2)") (class "Default")
      (node (ref "TX/RX") (pin "2") (pinfunction "2_2") (pintype "passive"))
    )
    (net (code "106") (name "unconnected-(TX/RX-Pad3)") (class "Default")
      (node (ref "TX/RX") (pin "3") (pinfunction "3_3") (pintype "passive"))
    )
    (net (code "107") (name "unconnected-(TX/RX-Pad4)") (class "Default")
      (node (ref "TX/RX") (pin "4") (pinfunction "4_4") (pintype "passive"))
    )
    (net (code "108") (name "unconnected-(TX/RX-Pad5)") (class "Default")
      (node (ref "TX/RX") (pin "5") (pinfunction "5_5") (pintype "passive"))
    )
    (net (code "109") (name "unconnected-(TX/RX-Pad6)") (class "Default")
      (node (ref "TX/RX") (pin "6") (pinfunction "6_6") (pintype "passive"))
    )
  )
)
